# v1.net
KiCad netlist of a schematic drawn in EAGLE
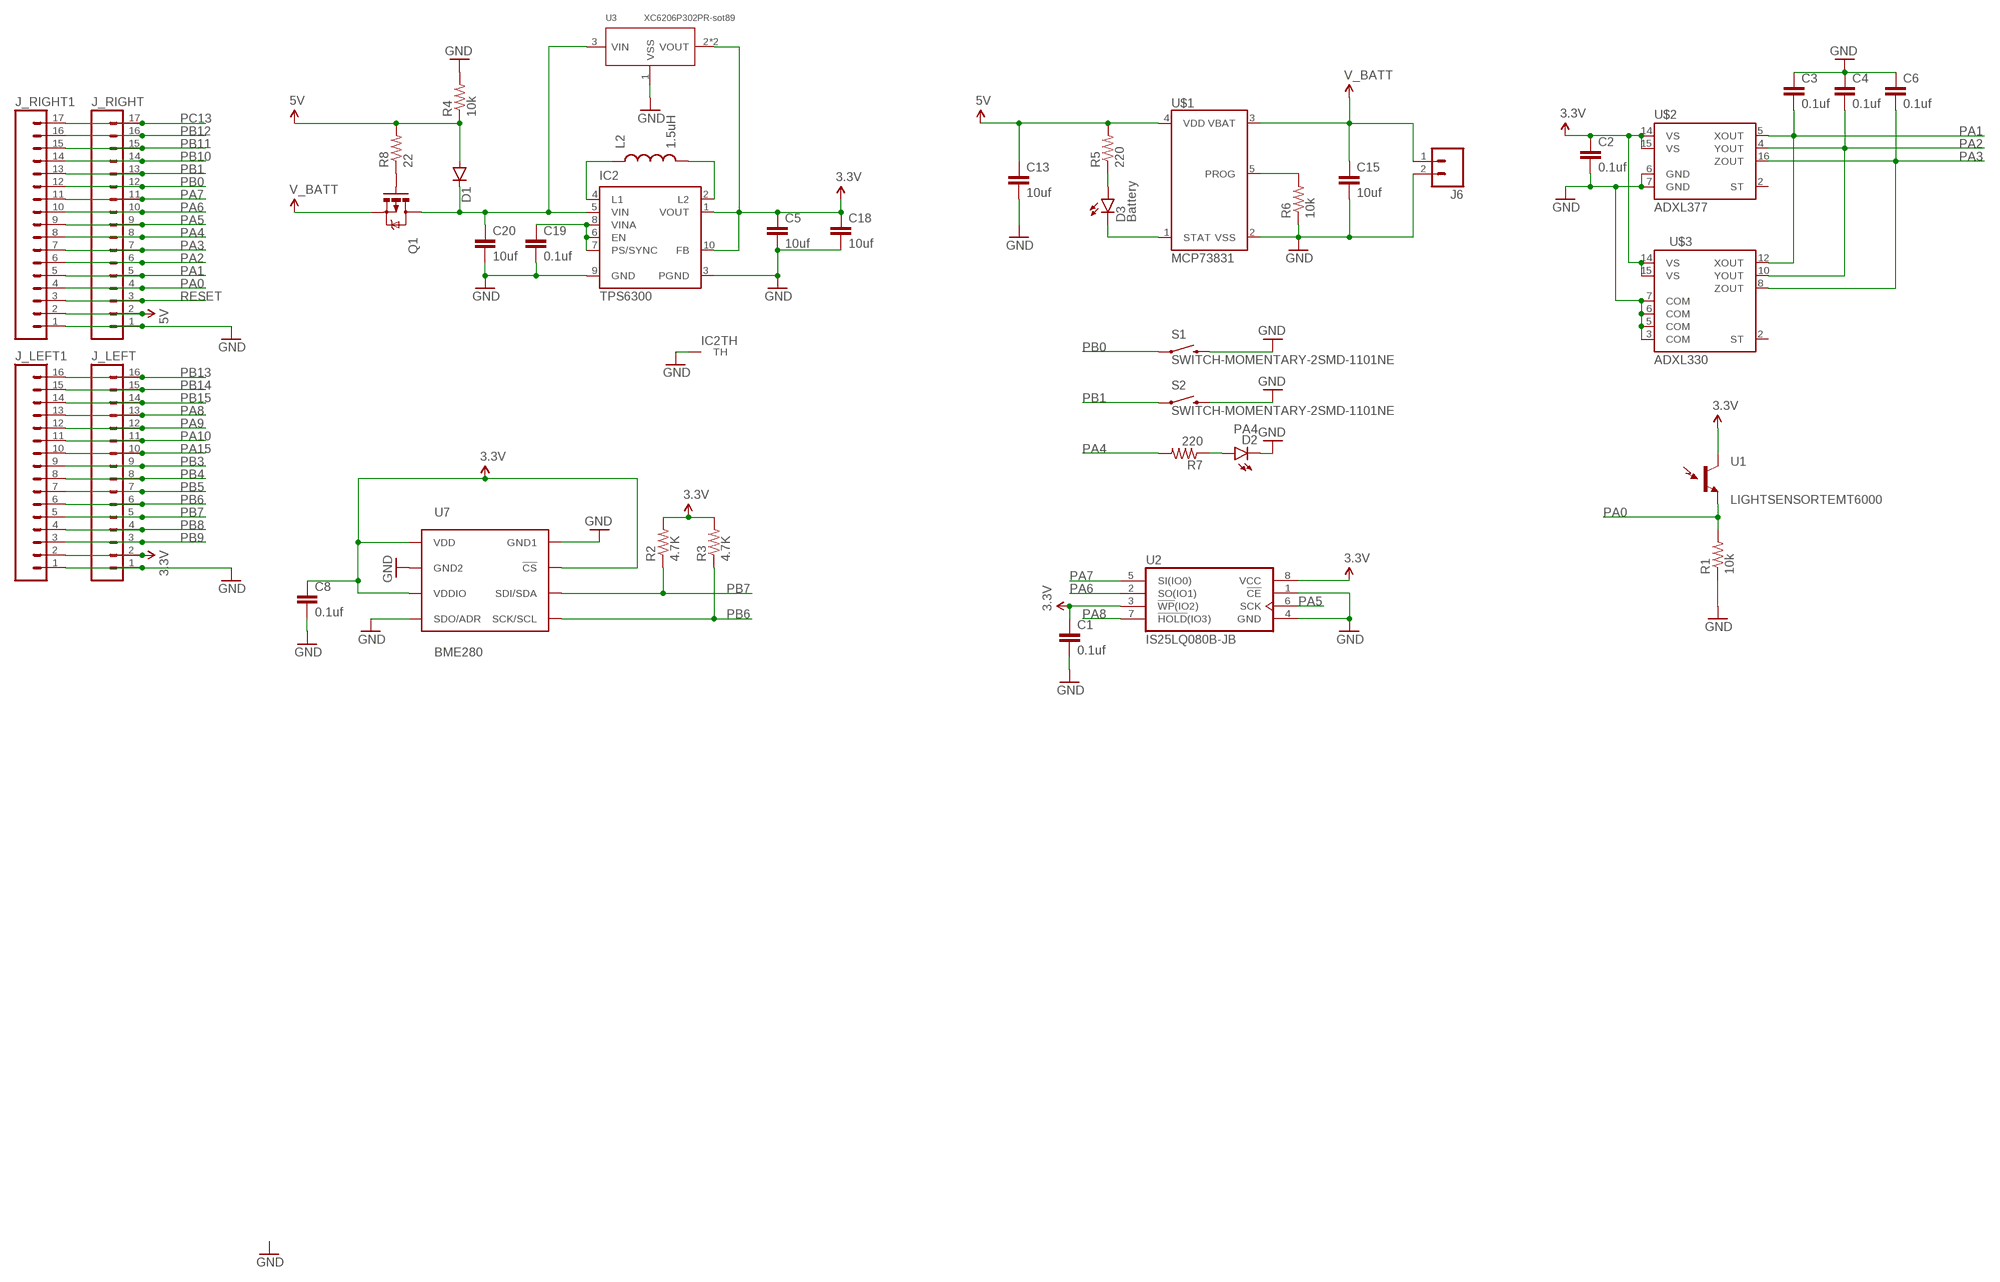
[diagram p0: schematic, sheet 1]

(export (version "E")
  (design (tool "Eeschema 10.0.6"))
  (components
    (comp (ref "C1")
      (value "0.1uf")
      (footprint "eagle-import:0805")
      (libsource (lib "eagle-import") (part "CAP0805"))
    )
    (comp (ref "C2")
      (value "0.1uf")
      (footprint "eagle-import:0805")
      (libsource (lib "eagle-import") (part "CAP0805"))
    )
    (comp (ref "C3")
      (value "0.1uf")
      (footprint "eagle-import:0805")
      (libsource (lib "eagle-import") (part "CAP0805"))
    )
    (comp (ref "C4")
      (value "0.1uf")
      (footprint "eagle-import:0805")
      (libsource (lib "eagle-import") (part "CAP0805"))
    )
    (comp (ref "C5")
      (value "10uf")
      (footprint "eagle-import:0805")
      (libsource (lib "eagle-import") (part "CAP0805"))
    )
    (comp (ref "C6")
      (value "0.1uf")
      (footprint "eagle-import:0805")
      (libsource (lib "eagle-import") (part "CAP0805"))
    )
    (comp (ref "C8")
      (value "0.1uf")
      (footprint "eagle-import:0805")
      (libsource (lib "eagle-import") (part "CAP0805"))
    )
    (comp (ref "C13")
      (value "10uf")
      (footprint "eagle-import:0805")
      (libsource (lib "eagle-import") (part "CAP0805"))
    )
    (comp (ref "C15")
      (value "10uf")
      (footprint "eagle-import:0805")
      (libsource (lib "eagle-import") (part "CAP0805"))
    )
    (comp (ref "C18")
      (value "10uf")
      (footprint "eagle-import:0805")
      (libsource (lib "eagle-import") (part "CAP0805"))
    )
    (comp (ref "C19")
      (value "0.1uf")
      (footprint "eagle-import:0805")
      (libsource (lib "eagle-import") (part "CAP0805"))
    )
    (comp (ref "C20")
      (value "10uf")
      (footprint "eagle-import:0805")
      (libsource (lib "eagle-import") (part "CAP0805"))
    )
    (comp (ref "D1")
      (value "DIODESOD123")
      (footprint "eagle-import:SOD-123")
      (libsource (lib "eagle-import") (part "DIODESOD123"))
    )
    (comp (ref "D2")
      (value "PA4")
      (footprint "eagle-import:LED-1206")
      (libsource (lib "eagle-import") (part "LED1206"))
    )
    (comp (ref "D3")
      (value "Battery")
      (footprint "eagle-import:LED-1206")
      (libsource (lib "eagle-import") (part "LED1206"))
    )
    (comp (ref "IC2")
      (value "TPS6300")
      (footprint "eagle-import:DRC-S-PVSON-N10")
      (fields (field (name "MPN") "TPS63000DRCTG4"))
      (libsource (lib "eagle-import") (part "TPS6300"))
    )
    (comp (ref "J6")
      (value "M021X02_NO_SILK")
      (footprint "eagle-import:1X02_NO_SILK")
      (libsource (lib "eagle-import") (part "M021X02_NO_SILK"))
    )
    (comp (ref "J_LEFT")
      (value "M161X16_NO_SILK")
      (footprint "eagle-import:1X16_NO_SILK")
      (libsource (lib "eagle-import") (part "M161X16_NO_SILK"))
    )
    (comp (ref "J_LEFT1")
      (value "M161X16_NO_SILK")
      (footprint "eagle-import:1X16_NO_SILK")
      (libsource (lib "eagle-import") (part "M161X16_NO_SILK"))
    )
    (comp (ref "J_RIGHT")
      (value "M17NOSILK")
      (footprint "eagle-import:1X17_NO_SILK")
      (libsource (lib "eagle-import") (part "M17NOSILK"))
    )
    (comp (ref "J_RIGHT1")
      (value "M17NOSILK")
      (footprint "eagle-import:1X17_NO_SILK")
      (libsource (lib "eagle-import") (part "M17NOSILK"))
    )
    (comp (ref "L2")
      (value "1.5uH")
      (footprint "eagle-import:SRN6045")
      (libsource (lib "eagle-import") (part "INDUCTORBOURNS_SRN6045"))
    )
    (comp (ref "Q1")
      (value "MOSFET-PCHANNEL")
      (footprint "eagle-import:SOT23-3")
      (libsource (lib "eagle-import") (part "MOSFET-PCHANNEL"))
    )
    (comp (ref "R1")
      (value "10k")
      (footprint "eagle-import:0805")
      (libsource (lib "eagle-import") (part "RESISTOR0805-RES"))
    )
    (comp (ref "R2")
      (value "4.7K")
      (footprint "eagle-import:0805")
      (libsource (lib "eagle-import") (part "RESISTOR0805-RES"))
    )
    (comp (ref "R3")
      (value "4.7K")
      (footprint "eagle-import:0805")
      (libsource (lib "eagle-import") (part "RESISTOR0805-RES"))
    )
    (comp (ref "R4")
      (value "10k")
      (footprint "eagle-import:0805")
      (libsource (lib "eagle-import") (part "RESISTOR0805-RES"))
    )
    (comp (ref "R5")
      (value "220")
      (footprint "eagle-import:0805")
      (libsource (lib "eagle-import") (part "RESISTOR0805-RES"))
    )
    (comp (ref "R6")
      (value "10k")
      (footprint "eagle-import:0805")
      (libsource (lib "eagle-import") (part "RESISTOR0805-RES"))
    )
    (comp (ref "R7")
      (value "220")
      (footprint "eagle-import:0805")
      (libsource (lib "eagle-import") (part "RESISTOR0805-RES"))
    )
    (comp (ref "R8")
      (value "22")
      (footprint "eagle-import:0805")
      (libsource (lib "eagle-import") (part "RESISTOR0805-RES"))
    )
    (comp (ref "S1")
      (value "SWITCH-MOMENTARY-2SMD-1101NE")
      (footprint "eagle-import:TACTILE-SWITCH-1101NE")
      (libsource (lib "eagle-import") (part "SWITCH-MOMENTARY-2SMD-1101NE"))
    )
    (comp (ref "S2")
      (value "SWITCH-MOMENTARY-2SMD-1101NE")
      (footprint "eagle-import:TACTILE-SWITCH-1101NE")
      (libsource (lib "eagle-import") (part "SWITCH-MOMENTARY-2SMD-1101NE"))
    )
    (comp (ref "U$1")
      (value "MCP73831")
      (footprint "eagle-import:SOT23-5")
      (libsource (lib "eagle-import") (part "MCP73831"))
    )
    (comp (ref "U$2")
      (value "ADXL377")
      (footprint "eagle-import:LFCSP_LQ-16")
      (libsource (lib "eagle-import") (part "ADXL377"))
    )
    (comp (ref "U$3")
      (value "ADXL330")
      (footprint "eagle-import:LFCSP-16")
      (libsource (lib "eagle-import") (part "ADXL330SMD"))
    )
    (comp (ref "U1")
      (value "LIGHTSENSORTEMT6000")
      (footprint "eagle-import:TEMT6000-SEN")
      (libsource (lib "eagle-import") (part "LIGHTSENSORTEMT6000"))
    )
    (comp (ref "U2")
      (value "IS25LQ080B-JB")
      (footprint "eagle-import:SO08-JB")
      (libsource (lib "eagle-import") (part "IS25LQ080B-JB"))
    )
    (comp (ref "U3")
      (value "XC6206P302PR-sot89")
      (footprint "eagle-import:SOT-89")
      (fields (field (name "MPN") "XC6206P302PR"))
      (libsource (lib "eagle-import") (part "PMIC-XC6206P302PR(SOT-89)"))
    )
    (comp (ref "U7")
      (value "BME280")
      (footprint "eagle-import:BME280_LGA")
      (libsource (lib "eagle-import") (part "BME280"))
    )
  )
  (nets
    (net (code "1") (name "/PA0") (class "Default")
      (node (ref "J_RIGHT") (pin "4") (pinfunction "4_4") (pintype "passive"))
      (node (ref "J_RIGHT1") (pin "4") (pinfunction "4_4") (pintype "passive"))
      (node (ref "R1") (pin "2") (pinfunction "2_2") (pintype "passive"))
      (node (ref "U1") (pin "EMITTER") (pinfunction "E1_EMITTER") (pintype "passive"))
    )
    (net (code "2") (name "/PA1") (class "Default")
      (node (ref "C3") (pin "2") (pinfunction "2_2") (pintype "passive"))
      (node (ref "J_RIGHT") (pin "5") (pinfunction "5_5") (pintype "passive"))
      (node (ref "J_RIGHT1") (pin "5") (pinfunction "5_5") (pintype "passive"))
      (node (ref "U$2") (pin "5") (pinfunction "XOUT_5") (pintype "bidirectional"))
      (node (ref "U$3") (pin "12") (pinfunction "XOUT_12") (pintype "bidirectional"))
    )
    (net (code "3") (name "/PA2") (class "Default")
      (node (ref "C4") (pin "2") (pinfunction "2_2") (pintype "passive"))
      (node (ref "J_RIGHT") (pin "6") (pinfunction "6_6") (pintype "passive"))
      (node (ref "J_RIGHT1") (pin "6") (pinfunction "6_6") (pintype "passive"))
      (node (ref "U$2") (pin "4") (pinfunction "YOUT_4") (pintype "bidirectional"))
      (node (ref "U$3") (pin "10") (pinfunction "YOUT_10") (pintype "bidirectional"))
    )
    (net (code "4") (name "/PA3") (class "Default")
      (node (ref "C6") (pin "2") (pinfunction "2_2") (pintype "passive"))
      (node (ref "J_RIGHT") (pin "7") (pinfunction "7_7") (pintype "passive"))
      (node (ref "J_RIGHT1") (pin "7") (pinfunction "7_7") (pintype "passive"))
      (node (ref "U$2") (pin "16") (pinfunction "ZOUT_16") (pintype "bidirectional"))
      (node (ref "U$3") (pin "8") (pinfunction "ZOUT_8") (pintype "bidirectional"))
    )
    (net (code "5") (name "/PA4") (class "Default")
      (node (ref "J_RIGHT") (pin "8") (pinfunction "8_8") (pintype "passive"))
      (node (ref "J_RIGHT1") (pin "8") (pinfunction "8_8") (pintype "passive"))
      (node (ref "R7") (pin "2") (pinfunction "2_2") (pintype "passive"))
    )
    (net (code "6") (name "/PA5") (class "Default")
      (node (ref "J_RIGHT") (pin "9") (pinfunction "9_9") (pintype "passive"))
      (node (ref "J_RIGHT1") (pin "9") (pinfunction "9_9") (pintype "passive"))
      (node (ref "U2") (pin "6") (pinfunction "SCK_6") (pintype "input"))
    )
    (net (code "7") (name "/PA6") (class "Default")
      (node (ref "J_RIGHT") (pin "10") (pinfunction "10_10") (pintype "passive"))
      (node (ref "J_RIGHT1") (pin "10") (pinfunction "10_10") (pintype "passive"))
      (node (ref "U2") (pin "2") (pinfunction "SO(IO1)_2") (pintype "bidirectional"))
    )
    (net (code "8") (name "/PA7") (class "Default")
      (node (ref "J_RIGHT") (pin "11") (pinfunction "11_11") (pintype "passive"))
      (node (ref "J_RIGHT1") (pin "11") (pinfunction "11_11") (pintype "passive"))
      (node (ref "U2") (pin "5") (pinfunction "SI(IO0)_5") (pintype "bidirectional"))
    )
    (net (code "9") (name "/PA8") (class "Default")
      (node (ref "J_LEFT") (pin "13") (pinfunction "13_13") (pintype "passive"))
      (node (ref "J_LEFT1") (pin "13") (pinfunction "13_13") (pintype "passive"))
      (node (ref "U2") (pin "7") (pinfunction "~{HOLD}(IO3)_7") (pintype "bidirectional"))
    )
    (net (code "10") (name "/PA9") (class "Default")
      (node (ref "J_LEFT") (pin "12") (pinfunction "12_12") (pintype "passive"))
      (node (ref "J_LEFT1") (pin "12") (pinfunction "12_12") (pintype "passive"))
    )
    (net (code "11") (name "/PA10") (class "Default")
      (node (ref "J_LEFT") (pin "11") (pinfunction "11_11") (pintype "passive"))
      (node (ref "J_LEFT1") (pin "11") (pinfunction "11_11") (pintype "passive"))
    )
    (net (code "12") (name "/PA15") (class "Default")
      (node (ref "J_LEFT") (pin "10") (pinfunction "10_10") (pintype "passive"))
      (node (ref "J_LEFT1") (pin "10") (pinfunction "10_10") (pintype "passive"))
    )
    (net (code "13") (name "/PB0") (class "Default")
      (node (ref "J_RIGHT") (pin "12") (pinfunction "12_12") (pintype "passive"))
      (node (ref "J_RIGHT1") (pin "12") (pinfunction "12_12") (pintype "passive"))
      (node (ref "S1") (pin "1") (pinfunction "1_1") (pintype "passive"))
    )
    (net (code "14") (name "/PB1") (class "Default")
      (node (ref "J_RIGHT") (pin "13") (pinfunction "13_13") (pintype "passive"))
      (node (ref "J_RIGHT1") (pin "13") (pinfunction "13_13") (pintype "passive"))
      (node (ref "S2") (pin "1") (pinfunction "1_1") (pintype "passive"))
    )
    (net (code "15") (name "/PB3") (class "Default")
      (node (ref "J_LEFT") (pin "9") (pinfunction "9_9") (pintype "passive"))
      (node (ref "J_LEFT1") (pin "9") (pinfunction "9_9") (pintype "passive"))
    )
    (net (code "16") (name "/PB4") (class "Default")
      (node (ref "J_LEFT") (pin "8") (pinfunction "8_8") (pintype "passive"))
      (node (ref "J_LEFT1") (pin "8") (pinfunction "8_8") (pintype "passive"))
    )
    (net (code "17") (name "/PB5") (class "Default")
      (node (ref "J_LEFT") (pin "7") (pinfunction "7_7") (pintype "passive"))
      (node (ref "J_LEFT1") (pin "7") (pinfunction "7_7") (pintype "passive"))
    )
    (net (code "18") (name "/PB6") (class "Default")
      (node (ref "J_LEFT") (pin "6") (pinfunction "6_6") (pintype "passive"))
      (node (ref "J_LEFT1") (pin "6") (pinfunction "6_6") (pintype "passive"))
      (node (ref "R3") (pin "1") (pinfunction "1_1") (pintype "passive"))
      (node (ref "U7") (pin "P$4") (pinfunction "SCK/SCL_P$4") (pintype "bidirectional"))
    )
    (net (code "19") (name "/PB7") (class "Default")
      (node (ref "J_LEFT") (pin "5") (pinfunction "5_5") (pintype "passive"))
      (node (ref "J_LEFT1") (pin "5") (pinfunction "5_5") (pintype "passive"))
      (node (ref "R2") (pin "1") (pinfunction "1_1") (pintype "passive"))
      (node (ref "U7") (pin "P$3") (pinfunction "SDI/SDA_P$3") (pintype "bidirectional"))
    )
    (net (code "20") (name "/PB8") (class "Default")
      (node (ref "J_LEFT") (pin "4") (pinfunction "4_4") (pintype "passive"))
      (node (ref "J_LEFT1") (pin "4") (pinfunction "4_4") (pintype "passive"))
    )
    (net (code "21") (name "/PB9") (class "Default")
      (node (ref "J_LEFT") (pin "3") (pinfunction "3_3") (pintype "passive"))
      (node (ref "J_LEFT1") (pin "3") (pinfunction "3_3") (pintype "passive"))
    )
    (net (code "22") (name "/PB10") (class "Default")
      (node (ref "J_RIGHT") (pin "14") (pinfunction "14_14") (pintype "passive"))
      (node (ref "J_RIGHT1") (pin "14") (pinfunction "14_14") (pintype "passive"))
    )
    (net (code "23") (name "/PB11") (class "Default")
      (node (ref "J_RIGHT") (pin "15") (pinfunction "15_15") (pintype "passive"))
      (node (ref "J_RIGHT1") (pin "15") (pinfunction "15_15") (pintype "passive"))
    )
    (net (code "24") (name "/PB12") (class "Default")
      (node (ref "J_RIGHT") (pin "16") (pinfunction "16_16") (pintype "passive"))
      (node (ref "J_RIGHT1") (pin "16") (pinfunction "16_16") (pintype "passive"))
    )
    (net (code "25") (name "/PB13") (class "Default")
      (node (ref "J_LEFT") (pin "16") (pinfunction "16_16") (pintype "passive"))
      (node (ref "J_LEFT1") (pin "16") (pinfunction "16_16") (pintype "passive"))
    )
    (net (code "26") (name "/PB14") (class "Default")
      (node (ref "J_LEFT") (pin "15") (pinfunction "15_15") (pintype "passive"))
      (node (ref "J_LEFT1") (pin "15") (pinfunction "15_15") (pintype "passive"))
    )
    (net (code "27") (name "/PB15") (class "Default")
      (node (ref "J_LEFT") (pin "14") (pinfunction "14_14") (pintype "passive"))
      (node (ref "J_LEFT1") (pin "14") (pinfunction "14_14") (pintype "passive"))
    )
    (net (code "28") (name "/PC13") (class "Default")
      (node (ref "J_RIGHT") (pin "17") (pinfunction "17_17") (pintype "passive"))
      (node (ref "J_RIGHT1") (pin "17") (pinfunction "17_17") (pintype "passive"))
    )
    (net (code "29") (name "/RESET") (class "Default")
      (node (ref "J_RIGHT") (pin "3") (pinfunction "3_3") (pintype "passive"))
      (node (ref "J_RIGHT1") (pin "3") (pinfunction "3_3") (pintype "passive"))
    )
    (net (code "30") (name "3.3V") (class "Default")
      (node (ref "C1") (pin "1") (pinfunction "1_1") (pintype "passive"))
      (node (ref "C18") (pin "1") (pinfunction "1_1") (pintype "passive"))
      (node (ref "C2") (pin "1") (pinfunction "1_1") (pintype "passive"))
      (node (ref "C5") (pin "1") (pinfunction "1_1") (pintype "passive"))
      (node (ref "C8") (pin "1") (pinfunction "1_1") (pintype "passive"))
      (node (ref "IC2") (pin "1") (pinfunction "VOUT_1") (pintype "output"))
      (node (ref "IC2") (pin "10") (pinfunction "FB_10") (pintype "input"))
      (node (ref "J_LEFT") (pin "2") (pinfunction "2_2") (pintype "passive"))
      (node (ref "J_LEFT1") (pin "2") (pinfunction "2_2") (pintype "passive"))
      (node (ref "R2") (pin "2") (pinfunction "2_2") (pintype "passive"))
      (node (ref "R3") (pin "2") (pinfunction "2_2") (pintype "passive"))
      (node (ref "U$2") (pin "14") (pinfunction "VS_14") (pintype "bidirectional"))
      (node (ref "U$2") (pin "15") (pinfunction "VS_15") (pintype "bidirectional"))
      (node (ref "U$3") (pin "14") (pinfunction "VS_14") (pintype "bidirectional"))
      (node (ref "U$3") (pin "15") (pinfunction "VS_15") (pintype "bidirectional"))
      (node (ref "U1") (pin "COLLECTOR") (pinfunction "C1_COLLECTOR") (pintype "passive"))
      (node (ref "U2") (pin "3") (pinfunction "~{WP}(IO2)_3") (pintype "bidirectional"))
      (node (ref "U2") (pin "8") (pinfunction "VCC_8") (pintype "power_in"))
      (node (ref "U3") (pin "2") (pinfunction "VOUT_2") (pintype "output"))
      (node (ref "U3") (pin "4") (pinfunction "VOUT_4") (pintype "output"))
      (node (ref "U7") (pin "P$2") (pinfunction "~{CS}_P$2") (pintype "bidirectional"))
      (node (ref "U7") (pin "P$6") (pinfunction "VDDIO_P$6") (pintype "bidirectional"))
      (node (ref "U7") (pin "P$8") (pinfunction "VDD_P$8") (pintype "bidirectional"))
    )
    (net (code "31") (name "5V") (class "Default")
      (node (ref "C13") (pin "1") (pinfunction "1_1") (pintype "passive"))
      (node (ref "D1") (pin "A") (pinfunction "A_A") (pintype "passive"))
      (node (ref "J_RIGHT") (pin "2") (pinfunction "2_2") (pintype "passive"))
      (node (ref "J_RIGHT1") (pin "2") (pinfunction "2_2") (pintype "passive"))
      (node (ref "R4") (pin "1") (pinfunction "1_1") (pintype "passive"))
      (node (ref "R5") (pin "2") (pinfunction "2_2") (pintype "passive"))
      (node (ref "R8") (pin "2") (pinfunction "2_2") (pintype "passive"))
      (node (ref "U$1") (pin "4") (pinfunction "VDD_4") (pintype "power_in"))
    )
    (net (code "32") (name "GND") (class "Default")
      (node (ref "C1") (pin "2") (pinfunction "2_2") (pintype "passive"))
      (node (ref "C13") (pin "2") (pinfunction "2_2") (pintype "passive"))
      (node (ref "C15") (pin "2") (pinfunction "2_2") (pintype "passive"))
      (node (ref "C18") (pin "2") (pinfunction "2_2") (pintype "passive"))
      (node (ref "C19") (pin "2") (pinfunction "2_2") (pintype "passive"))
      (node (ref "C2") (pin "2") (pinfunction "2_2") (pintype "passive"))
      (node (ref "C20") (pin "2") (pinfunction "2_2") (pintype "passive"))
      (node (ref "C3") (pin "1") (pinfunction "1_1") (pintype "passive"))
      (node (ref "C4") (pin "1") (pinfunction "1_1") (pintype "passive"))
      (node (ref "C5") (pin "2") (pinfunction "2_2") (pintype "passive"))
      (node (ref "C6") (pin "1") (pinfunction "1_1") (pintype "passive"))
      (node (ref "C8") (pin "2") (pinfunction "2_2") (pintype "passive"))
      (node (ref "D2") (pin "C") (pinfunction "C_C") (pintype "passive"))
      (node (ref "IC2") (pin "3") (pinfunction "PGND_3") (pintype "power_in"))
      (node (ref "IC2") (pin "9") (pinfunction "GND_9") (pintype "power_in"))
      (node (ref "IC2") (pin "TH") (pinfunction "TH_TH") (pintype "passive"))
      (node (ref "J6") (pin "2") (pinfunction "2_2") (pintype "passive"))
      (node (ref "J_LEFT") (pin "1") (pinfunction "1_1") (pintype "passive"))
      (node (ref "J_LEFT1") (pin "1") (pinfunction "1_1") (pintype "passive"))
      (node (ref "J_RIGHT") (pin "1") (pinfunction "1_1") (pintype "passive"))
      (node (ref "J_RIGHT1") (pin "1") (pinfunction "1_1") (pintype "passive"))
      (node (ref "R1") (pin "1") (pinfunction "1_1") (pintype "passive"))
      (node (ref "R4") (pin "2") (pinfunction "2_2") (pintype "passive"))
      (node (ref "R6") (pin "1") (pinfunction "1_1") (pintype "passive"))
      (node (ref "S1") (pin "2") (pinfunction "2_2") (pintype "passive"))
      (node (ref "S2") (pin "2") (pinfunction "2_2") (pintype "passive"))
      (node (ref "U$1") (pin "2") (pinfunction "VSS_2") (pintype "power_in"))
      (node (ref "U$2") (pin "6") (pinfunction "GND_6") (pintype "bidirectional"))
      (node (ref "U$2") (pin "7") (pinfunction "GND_7") (pintype "bidirectional"))
      (node (ref "U$3") (pin "3") (pinfunction "COM_3") (pintype "bidirectional"))
      (node (ref "U$3") (pin "5") (pinfunction "COM_5") (pintype "bidirectional"))
      (node (ref "U$3") (pin "6") (pinfunction "COM_6") (pintype "bidirectional"))
      (node (ref "U$3") (pin "7") (pinfunction "COM_7") (pintype "bidirectional"))
      (node (ref "U2") (pin "1") (pinfunction "~{CE}_1") (pintype "input"))
      (node (ref "U2") (pin "4") (pinfunction "GND_4") (pintype "power_in"))
      (node (ref "U3") (pin "1") (pinfunction "VSS_1") (pintype "power_in"))
      (node (ref "U7") (pin "P$1") (pinfunction "GND1_P$1") (pintype "bidirectional"))
      (node (ref "U7") (pin "P$5") (pinfunction "SDO/ADR_P$5") (pintype "bidirectional"))
      (node (ref "U7") (pin "P$7") (pinfunction "GND2_P$7") (pintype "bidirectional"))
    )
    (net (code "33") (name "Net-(D2-PadA)") (class "Default")
      (node (ref "D2") (pin "A") (pinfunction "A_A") (pintype "passive"))
      (node (ref "R7") (pin "1") (pinfunction "1_1") (pintype "passive"))
    )
    (net (code "34") (name "Net-(D3-PadA)") (class "Default")
      (node (ref "D3") (pin "A") (pinfunction "A_A") (pintype "passive"))
      (node (ref "R5") (pin "1") (pinfunction "1_1") (pintype "passive"))
    )
    (net (code "35") (name "Net-(IC2A-EN)") (class "Default")
      (node (ref "C19") (pin "1") (pinfunction "1_1") (pintype "passive"))
      (node (ref "IC2") (pin "6") (pinfunction "EN_6") (pintype "input"))
      (node (ref "IC2") (pin "7") (pinfunction "PS/SYNC_7") (pintype "input"))
      (node (ref "IC2") (pin "8") (pinfunction "VINA_8") (pintype "input"))
    )
    (net (code "36") (name "Net-(IC2A-L1)") (class "Default")
      (node (ref "IC2") (pin "4") (pinfunction "L1_4") (pintype "passive"))
      (node (ref "L2") (pin "1") (pinfunction "1_1") (pintype "passive"))
    )
    (net (code "37") (name "Net-(IC2A-L2)") (class "Default")
      (node (ref "IC2") (pin "2") (pinfunction "L2_2") (pintype "passive"))
      (node (ref "L2") (pin "2") (pinfunction "2_2") (pintype "passive"))
    )
    (net (code "38") (name "Net-(IC2A-VIN)") (class "Default")
      (node (ref "C20") (pin "1") (pinfunction "1_1") (pintype "passive"))
      (node (ref "D1") (pin "C") (pinfunction "C_C") (pintype "passive"))
      (node (ref "IC2") (pin "5") (pinfunction "VIN_5") (pintype "input"))
      (node (ref "Q1") (pin "3") (pinfunction "D_3") (pintype "passive"))
      (node (ref "U3") (pin "3") (pinfunction "VIN_3") (pintype "input"))
    )
    (net (code "39") (name "Net-(Q1-G)") (class "Default")
      (node (ref "Q1") (pin "1") (pinfunction "G_1") (pintype "passive"))
      (node (ref "R8") (pin "1") (pinfunction "1_1") (pintype "passive"))
    )
    (net (code "40") (name "Net-(U$1-PROG)") (class "Default")
      (node (ref "R6") (pin "2") (pinfunction "2_2") (pintype "passive"))
      (node (ref "U$1") (pin "5") (pinfunction "PROG_5") (pintype "input"))
    )
    (net (code "41") (name "Net-(U$1-STAT)") (class "Default")
      (node (ref "D3") (pin "C") (pinfunction "C_C") (pintype "passive"))
      (node (ref "U$1") (pin "1") (pinfunction "STAT_1") (pintype "output"))
    )
    (net (code "42") (name "V_BATT") (class "Default")
      (node (ref "C15") (pin "1") (pinfunction "1_1") (pintype "passive"))
      (node (ref "J6") (pin "1") (pinfunction "1_1") (pintype "passive"))
      (node (ref "Q1") (pin "2") (pinfunction "S_2") (pintype "passive"))
      (node (ref "U$1") (pin "3") (pinfunction "VBAT_3") (pintype "power_in"))
    )
    (net (code "43") (name "unconnected-(U$2-ST-Pad2)") (class "Default")
      (node (ref "U$2") (pin "2") (pinfunction "ST_2") (pintype "bidirectional"))
    )
    (net (code "44") (name "unconnected-(U$3-ST-Pad2)") (class "Default")
      (node (ref "U$3") (pin "2") (pinfunction "ST_2") (pintype "bidirectional"))
    )
  )
)
